# 05_Power_Supply_Tracker.net
KiCad netlist of a schematic drawn in Altium Designer
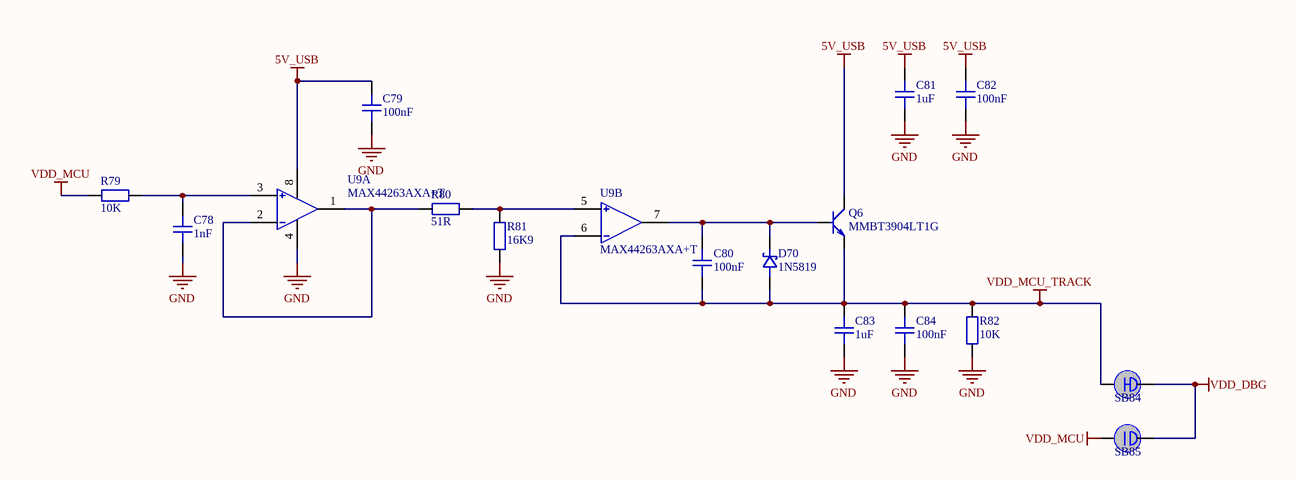
[diagram p0: [05]Power Supply Tracker.SchDoc]

(export (version "E")
  (design (tool "Eeschema 10.0.6"))
  (components
    (comp (ref "C78")
      (value "1nF")
      (footprint "CAPC1005L")
      (description "Surface Mount Unpolarized Capacitor")
      (libsource (lib "Discrete") (part "CAP_CHP"))
    )
    (comp (ref "C79")
      (value "100nF")
      (footprint "CAPC1005L")
      (description "Surface Mount Unpolarized Capacitor")
      (libsource (lib "Discrete") (part "CAP_CHP"))
    )
    (comp (ref "C80")
      (value "100nF")
      (footprint "CAPC1005L")
      (description "Surface Mount Unpolarized Capacitor")
      (libsource (lib "Discrete") (part "CAP_CHP"))
    )
    (comp (ref "C81")
      (value "1uF")
      (footprint "CAPC1005L")
      (description "Surface Mount Unpolarized Capacitor")
      (libsource (lib "Discrete") (part "CAP_CHP"))
    )
    (comp (ref "C82")
      (value "100nF")
      (footprint "CAPC1005L")
      (description "Surface Mount Unpolarized Capacitor")
      (libsource (lib "Discrete") (part "CAP_CHP"))
    )
    (comp (ref "C83")
      (value "1uF")
      (footprint "CAPC1005L")
      (description "Surface Mount Unpolarized Capacitor")
      (libsource (lib "Discrete") (part "CAP_CHP"))
    )
    (comp (ref "C84")
      (value "100nF")
      (footprint "CAPC1005L")
      (description "Surface Mount Unpolarized Capacitor")
      (libsource (lib "Discrete") (part "CAP_CHP"))
    )
    (comp (ref "D70")
      (value "1N5819")
      (footprint "SOD2512X100L")
      (description "Surface Mount Diode")
      (libsource (lib "Discrete") (part "SKT_SMD"))
    )
    (comp (ref "Q6")
      (value "MMBT3904LT1G")
      (footprint "SOT23-3N")
      (description "Surface Mount NPN Transistor")
      (libsource (lib "Discrete") (part "TRAN_NPN"))
    )
    (comp (ref "R79")
      (value "10K")
      (footprint "RESC1005L")
      (description "Surface Mount Resistor")
      (libsource (lib "Discrete") (part "RES_CHP"))
    )
    (comp (ref "R80")
      (value "51R")
      (footprint "RESC1005L")
      (description "Surface Mount Resistor")
      (libsource (lib "Discrete") (part "RES_CHP"))
    )
    (comp (ref "R81")
      (value "16K9")
      (footprint "RESC1005L")
      (description "Surface Mount Resistor")
      (libsource (lib "Discrete") (part "RES_CHP"))
    )
    (comp (ref "R82")
      (value "10K")
      (footprint "RESC1005L")
      (description "Surface Mount Resistor")
      (libsource (lib "Discrete") (part "RES_CHP"))
    )
    (comp (ref "SB84")
      (value "SBS")
      (footprint "SBS")
      (description "Short-circuit soldering bridge")
      (libsource (lib "Connector") (part "SBS"))
    )
    (comp (ref "SB85")
      (value "SBO")
      (footprint "SBO")
      (description "Open-circuit soldering bridge")
      (libsource (lib "Connector") (part "SBO"))
    )
    (comp (ref "U9")
      (value "MAX44263AXA+T")
      (footprint "SC-70-8")
      (description "General Purpose Amplifier 2 Circuit Rail-to-Rail")
      (libsource (lib "IC") (part "MAX44263"))
    )
  )
  (nets
    (net (code "1") (name "5V_USB") (class "Default")
      (node (ref "C79") (pin "2") (pinfunction "2_2") (pintype "passive"))
      (node (ref "C81") (pin "2") (pinfunction "2_2") (pintype "passive"))
      (node (ref "C82") (pin "2") (pinfunction "2_2") (pintype "passive"))
      (node (ref "Q6") (pin "3") (pinfunction "3_3") (pintype "passive"))
      (node (ref "U9") (pin "8") (pinfunction "8_8") (pintype "power_in"))
    )
    (net (code "2") (name "GND") (class "Default")
      (node (ref "C78") (pin "1") (pinfunction "1_1") (pintype "passive"))
      (node (ref "C79") (pin "1") (pinfunction "1_1") (pintype "passive"))
      (node (ref "C81") (pin "1") (pinfunction "1_1") (pintype "passive"))
      (node (ref "C82") (pin "1") (pinfunction "1_1") (pintype "passive"))
      (node (ref "C83") (pin "1") (pinfunction "1_1") (pintype "passive"))
      (node (ref "C84") (pin "1") (pinfunction "1_1") (pintype "passive"))
      (node (ref "R81") (pin "1") (pinfunction "1_1") (pintype "passive"))
      (node (ref "R82") (pin "1") (pinfunction "1_1") (pintype "passive"))
      (node (ref "U9") (pin "4") (pinfunction "4_4") (pintype "power_in"))
    )
    (net (code "3") (name "Net-(U9A-OUT)") (class "Default")
      (node (ref "R80") (pin "1") (pinfunction "1_1") (pintype "passive"))
      (node (ref "U9") (pin "1") (pinfunction "OUT_1") (pintype "passive"))
      (node (ref "U9") (pin "2") (pinfunction "VIN-_2") (pintype "passive"))
    )
    (net (code "4") (name "Net-(U9A-VIN+)") (class "Default")
      (node (ref "C78") (pin "2") (pinfunction "2_2") (pintype "passive"))
      (node (ref "R79") (pin "2") (pinfunction "2_2") (pintype "passive"))
      (node (ref "U9") (pin "3") (pinfunction "VIN+_3") (pintype "passive"))
    )
    (net (code "5") (name "Net-(U9B-OUT)") (class "Default")
      (node (ref "C80") (pin "2") (pinfunction "2_2") (pintype "passive"))
      (node (ref "D70") (pin "1") (pinfunction "1_1") (pintype "passive"))
      (node (ref "Q6") (pin "1") (pinfunction "1_1") (pintype "passive"))
      (node (ref "U9") (pin "7") (pinfunction "OUT_7") (pintype "passive"))
    )
    (net (code "6") (name "Net-(U9B-VIN+)") (class "Default")
      (node (ref "R80") (pin "2") (pinfunction "2_2") (pintype "passive"))
      (node (ref "R81") (pin "2") (pinfunction "2_2") (pintype "passive"))
      (node (ref "U9") (pin "5") (pinfunction "VIN+_5") (pintype "passive"))
    )
    (net (code "7") (name "VDD_DBG") (class "Default")
      (node (ref "SB84") (pin "2") (pinfunction "2_2") (pintype "passive"))
      (node (ref "SB85") (pin "2") (pinfunction "2_2") (pintype "passive"))
    )
    (net (code "8") (name "VDD_MCU") (class "Default")
      (node (ref "R79") (pin "1") (pinfunction "1_1") (pintype "passive"))
      (node (ref "SB85") (pin "1") (pinfunction "1_1") (pintype "passive"))
    )
    (net (code "9") (name "VDD_MCU_TRACK") (class "Default")
      (node (ref "C80") (pin "1") (pinfunction "1_1") (pintype "passive"))
      (node (ref "C83") (pin "2") (pinfunction "2_2") (pintype "passive"))
      (node (ref "C84") (pin "2") (pinfunction "2_2") (pintype "passive"))
      (node (ref "D70") (pin "2") (pinfunction "2_2") (pintype "passive"))
      (node (ref "Q6") (pin "2") (pinfunction "2_2") (pintype "passive"))
      (node (ref "R82") (pin "2") (pinfunction "2_2") (pintype "passive"))
      (node (ref "SB84") (pin "1") (pinfunction "1_1") (pintype "passive"))
      (node (ref "U9") (pin "6") (pinfunction "VIN-_6") (pintype "passive"))
    )
  )
)
